# 6-SON.net
KiCad netlist of a schematic drawn in Altium Designer
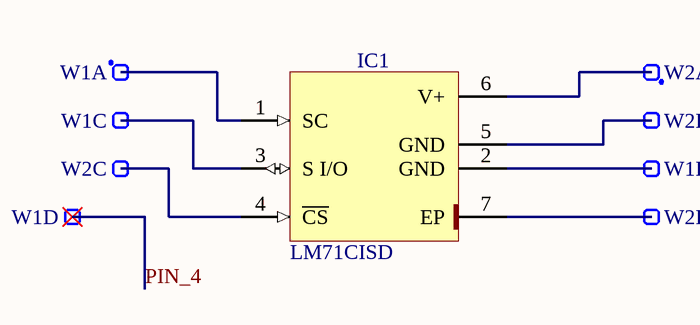
[diagram p0: 6-SON.SchDoc]

(export (version "E")
  (design (tool "Eeschema 10.0.6"))
  (components
    (comp (ref "IC1")
      (value "LM71CISD")
      (footprint "SON95P300X300X80-7N-R160X210-NGG0006A")
      (description "LM71/LM71-Q1 SPI/MICROWIRE 13-Bit Plus Sign Temperature Sensor")
      (fields
        (field (name "MANUFACTURER") "TEXAS INSTRUMENTS")
        (field (name "DEVICE") "LM71CISD")
        (field (name "AUTHOR") "LNLS DIG LOS")
      )
      (libsource (lib "ICs And Semiconductors_LNLS") (part "LM71"))
    )
    (comp (ref "W1")
      (value "Header 4")
      (footprint "SAMTEC_TSW-104-23-L-S")
      (description "4 Mini Wire-Wrap Contact Strip Header")
      (fields
        (field (name "PART NUMBER") "SAMTEC_TSW-104-23-L-S")
        (field (name "MANUFACTURER") "SAMTEC")
        (field (name "AUTHOR") "CERN DEM JLC")
      )
      (libsource (lib "Connectors") (part "Wire-Wrap Contact x4"))
    )
    (comp (ref "W2")
      (value "Header 4")
      (footprint "SAMTEC_TSW-104-23-L-S")
      (description "4 Mini Wire-Wrap Contact Strip Header")
      (fields
        (field (name "PART NUMBER") "SAMTEC_TSW-104-23-L-S")
        (field (name "MANUFACTURER") "SAMTEC")
        (field (name "AUTHOR") "CERN DEM JLC")
      )
      (libsource (lib "Connectors") (part "Wire-Wrap Contact x4"))
    )
  )
  (nets
    (net (code "1") (name "/PIN_4") (class "Default")
      (node (ref "W1") (pin "4") (pinfunction "4_4") (pintype "bidirectional+no_connect"))
    )
    (net (code "2") (name "Net-(IC1-EP)") (class "Default")
      (node (ref "IC1") (pin "7") (pinfunction "EP_7") (pintype "power_in"))
      (node (ref "W2") (pin "4") (pinfunction "4_4") (pintype "bidirectional"))
    )
    (net (code "3") (name "Net-(IC1-GND-Pad2)") (class "Default")
      (node (ref "IC1") (pin "2") (pinfunction "GND_2") (pintype "power_in"))
      (node (ref "W1") (pin "2") (pinfunction "2_2") (pintype "bidirectional"))
    )
    (net (code "4") (name "Net-(IC1-GND-Pad5)") (class "Default")
      (node (ref "IC1") (pin "5") (pinfunction "GND_5") (pintype "power_in"))
      (node (ref "W2") (pin "2") (pinfunction "2_2") (pintype "bidirectional"))
    )
    (net (code "5") (name "Net-(IC1-SC)") (class "Default")
      (node (ref "IC1") (pin "1") (pinfunction "SC_1") (pintype "input"))
      (node (ref "W1") (pin "1") (pinfunction "1_1") (pintype "bidirectional"))
    )
    (net (code "6") (name "Net-(IC1-S_I{slash}O)") (class "Default")
      (node (ref "IC1") (pin "3") (pinfunction "S_I/O_3") (pintype "bidirectional"))
      (node (ref "W1") (pin "3") (pinfunction "3_3") (pintype "bidirectional"))
    )
    (net (code "7") (name "Net-(IC1-V+)") (class "Default")
      (node (ref "IC1") (pin "6") (pinfunction "V+_6") (pintype "power_in"))
      (node (ref "W2") (pin "1") (pinfunction "1_1") (pintype "bidirectional"))
    )
    (net (code "8") (name "Net-(IC1-~{CS})") (class "Default")
      (node (ref "IC1") (pin "4") (pinfunction "~{CS}_4") (pintype "input"))
      (node (ref "W2") (pin "3") (pinfunction "3_3") (pintype "bidirectional"))
    )
  )
)
